# ModMicroController.net
KiCad netlist of a schematic drawn in Altium Designer
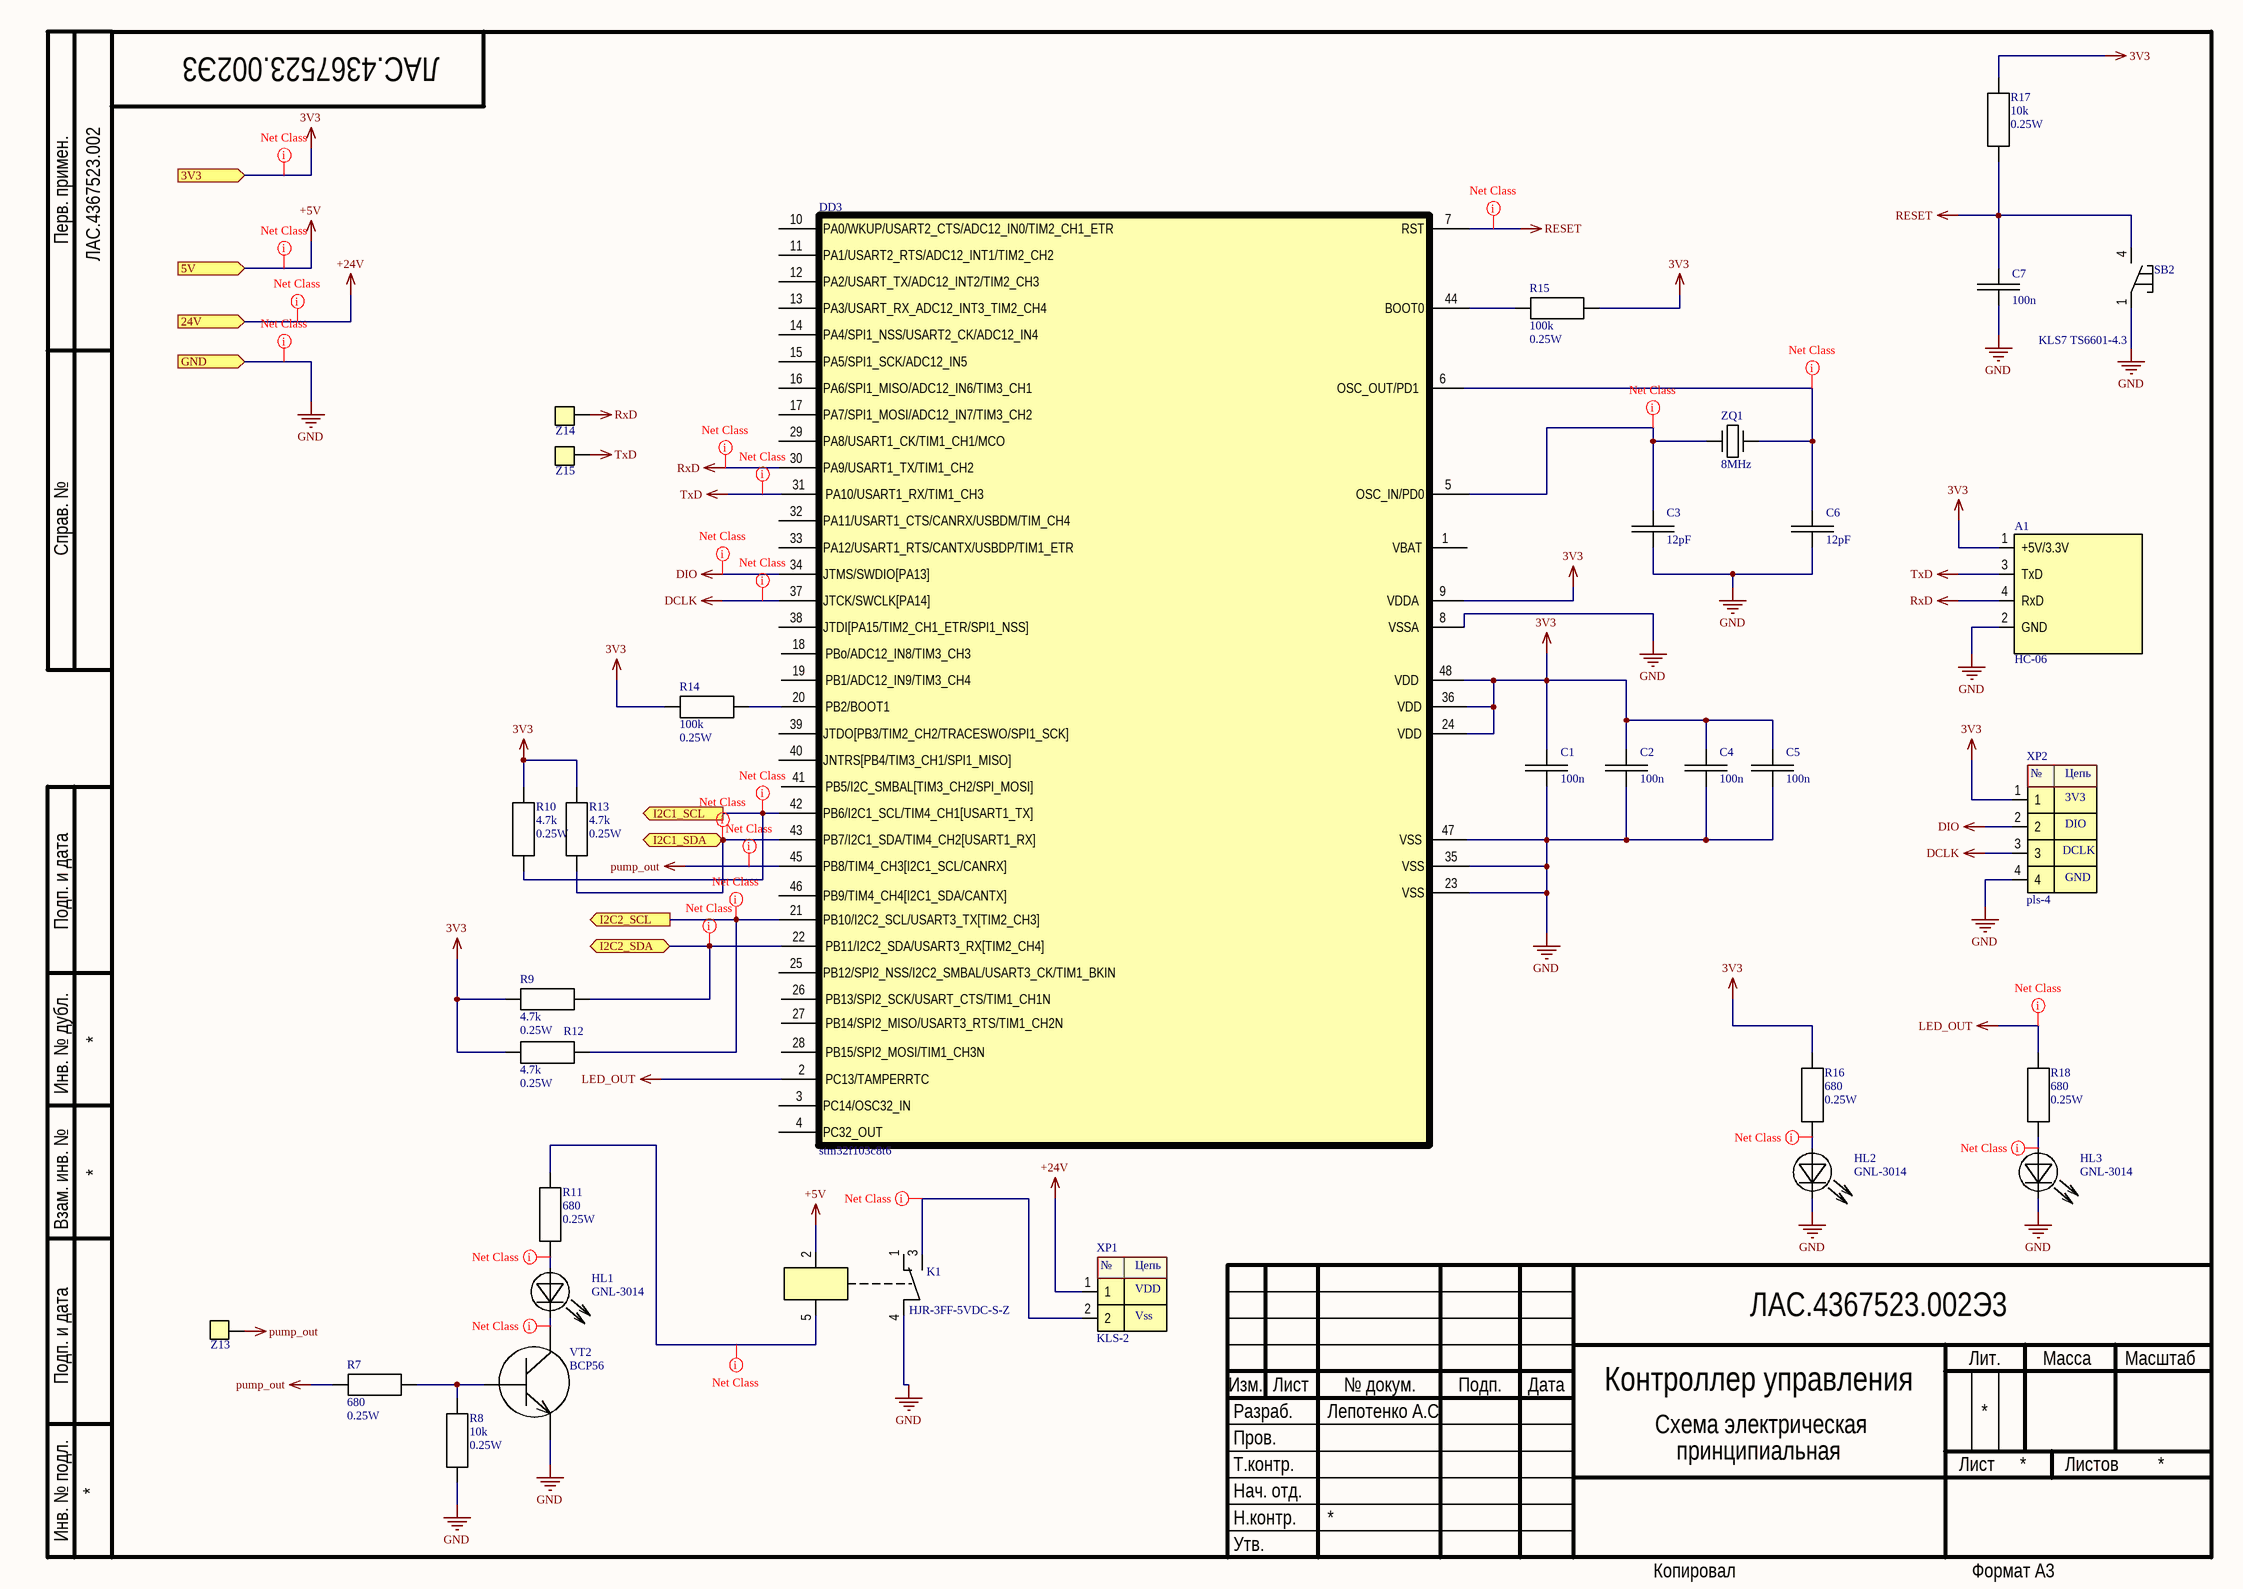
[diagram p0: ModMicroController.SchDoc]

(export (version "E")
  (design (tool "Eeschema 10.0.6"))
  (components
    (comp (ref "A1")
      (value "HC-06")
      (footprint "HC-06")
      (fields (field (name "MANUFACTURER") "china"))
      (libsource (lib "SchlibUGO") (part "HC-06"))
    )
    (comp (ref "C1")
      (value "100n")
      (footprint "CAP1206")
      (fields
        (field (name "VOLTAGE") "50V")
        (field (name "PART NUMBER") "CL31B104KBCNNNC")
        (field (name "MANUFACTURER") "Samsung")
      )
      (libsource (lib "SchlibUGO") (part "Capasitor"))
    )
    (comp (ref "C2")
      (value "100n")
      (footprint "CAP1206")
      (fields
        (field (name "VOLTAGE") "50V")
        (field (name "PART NUMBER") "CL31B104KBCNNNC")
        (field (name "MANUFACTURER") "Samsung")
      )
      (libsource (lib "SchlibUGO") (part "Capasitor"))
    )
    (comp (ref "C3")
      (value "12pF")
      (footprint "CAP1206")
      (fields
        (field (name "VOLTAGE") "50V")
        (field (name "PART NUMBER") "1206120NPO")
        (field (name "MANUFACTURER") "Samsung")
      )
      (libsource (lib "SchlibUGO") (part "Capasitor"))
    )
    (comp (ref "C4")
      (value "100n")
      (footprint "CAP1206")
      (fields
        (field (name "VOLTAGE") "50V")
        (field (name "PART NUMBER") "CL31B104KBCNNNC")
        (field (name "MANUFACTURER") "Samsung")
      )
      (libsource (lib "SchlibUGO") (part "Capasitor"))
    )
    (comp (ref "C5")
      (value "100n")
      (footprint "CAP1206")
      (fields
        (field (name "VOLTAGE") "50V")
        (field (name "PART NUMBER") "CL31B104KBCNNNC")
        (field (name "MANUFACTURER") "Samsung")
      )
      (libsource (lib "SchlibUGO") (part "Capasitor"))
    )
    (comp (ref "C6")
      (value "12pF")
      (footprint "CAP1206")
      (fields
        (field (name "VOLTAGE") "50V")
        (field (name "PART NUMBER") "1206120NPO")
        (field (name "MANUFACTURER") "Samsung")
      )
      (libsource (lib "SchlibUGO") (part "Capasitor"))
    )
    (comp (ref "C7") (value "100n") (footprint "CAP1206") (libsource (lib "SchlibUGO") (part "Capasitor")))
    (comp (ref "DD3")
      (value "stm32f103c8t6")
      (footprint "LQFP48")
      (fields (field (name "MANUFACTURER") "STM"))
      (libsource (lib "SchlibUGO") (part "stm32f103c8t6"))
    )
    (comp (ref "HL1")
      (value "GNL-3014")
      (footprint "GNL-3014")
      (fields (field (name "PART NUMBER") "GNL-3014SRD") (field (name "MANUFACTURER") "G-NOR"))
      (libsource (lib "SchlibUGO") (part "LED"))
    )
    (comp (ref "HL2")
      (value "GNL-3014")
      (footprint "GNL-3014")
      (fields (field (name "PART NUMBER") "GNL-3014SRD") (field (name "MANUFACTURER") "G-NOR"))
      (libsource (lib "SchlibUGO") (part "LED"))
    )
    (comp (ref "HL3")
      (value "GNL-3014")
      (footprint "GNL-3014")
      (fields (field (name "PART NUMBER") "GNL-3014SRD") (field (name "MANUFACTURER") "G-NOR"))
      (libsource (lib "SchlibUGO") (part "LED"))
    )
    (comp (ref "K1")
      (value "HJR-3FF-5VDC-S-Z")
      (footprint "HJR-3FF")
      (fields (field (name "MANUFACTURER") "TIANBO"))
      (libsource (lib "SchlibUGO") (part "HJR-3FF-5VDC-S-Z"))
    )
    (comp (ref "R7")
      (value "680")
      (footprint "1206")
      (fields
        (field (name "MANUFACTURER") "YAGEO")
        (field (name "PART NUMBER") "RC1206JR-07680RL")
        (field (name "POWER") "0.25W")
      )
      (libsource (lib "SchlibUGO") (part "Resistor"))
    )
    (comp (ref "R8")
      (value "10k")
      (footprint "1206")
      (fields
        (field (name "MANUFACTURER") "YAGEO")
        (field (name "PART NUMBER") "RC1206FR-0710KL")
        (field (name "POWER") "0.25W")
      )
      (libsource (lib "SchlibUGO") (part "Resistor"))
    )
    (comp (ref "R9")
      (value "4.7k")
      (footprint "1206")
      (fields
        (field (name "MANUFACTURER") "YAGEO")
        (field (name "PART NUMBER") "RC1206JR-074K7L")
        (field (name "POWER") "0.25W")
        (field (name "Comment") "4k7")
      )
      (libsource (lib "SchlibUGO") (part "Resistor"))
    )
    (comp (ref "R10")
      (value "4.7k")
      (footprint "1206")
      (fields
        (field (name "MANUFACTURER") "YAGEO")
        (field (name "PART NUMBER") "RC1206JR-074K7L")
        (field (name "POWER") "0.25W")
        (field (name "Comment") "4k7")
      )
      (libsource (lib "SchlibUGO") (part "Resistor"))
    )
    (comp (ref "R11")
      (value "680")
      (footprint "1206")
      (fields
        (field (name "MANUFACTURER") "YAGEO")
        (field (name "PART NUMBER") "RC1206JR-07680RL")
        (field (name "POWER") "0.25W")
      )
      (libsource (lib "SchlibUGO") (part "Resistor"))
    )
    (comp (ref "R12")
      (value "4.7k")
      (footprint "1206")
      (fields
        (field (name "MANUFACTURER") "YAGEO")
        (field (name "PART NUMBER") "RC1206JR-074K7L")
        (field (name "POWER") "0.25W")
        (field (name "Comment") "4k7")
      )
      (libsource (lib "SchlibUGO") (part "Resistor"))
    )
    (comp (ref "R13")
      (value "4.7k")
      (footprint "1206")
      (fields
        (field (name "MANUFACTURER") "YAGEO")
        (field (name "PART NUMBER") "RC1206JR-074K7L")
        (field (name "POWER") "0.25W")
        (field (name "Comment") "4k7")
      )
      (libsource (lib "SchlibUGO") (part "Resistor"))
    )
    (comp (ref "R14")
      (value "100k")
      (footprint "1206")
      (fields
        (field (name "MANUFACTURER") "YAGEO")
        (field (name "PART NUMBER") "RC1206JR-07100KL")
        (field (name "POWER") "0.25W")
        (field (name "Comment") "Resistor")
      )
      (libsource (lib "SchlibUGO") (part "Resistor"))
    )
    (comp (ref "R15")
      (value "100k")
      (footprint "1206")
      (fields
        (field (name "MANUFACTURER") "YAGEO")
        (field (name "PART NUMBER") "RC1206JR-07100KL")
        (field (name "POWER") "0.25W")
        (field (name "Comment") "Resistor")
      )
      (libsource (lib "SchlibUGO") (part "Resistor"))
    )
    (comp (ref "R16")
      (value "680")
      (footprint "1206")
      (fields
        (field (name "MANUFACTURER") "YAGEO")
        (field (name "PART NUMBER") "RC1206JR-07680RL")
        (field (name "POWER") "0.25W")
      )
      (libsource (lib "SchlibUGO") (part "Resistor"))
    )
    (comp (ref "R17")
      (value "10k")
      (footprint "1206")
      (fields
        (field (name "MANUFACTURER") "YAGEO")
        (field (name "PART NUMBER") "RC1206FR-0710KL")
        (field (name "POWER") "0.25W")
      )
      (libsource (lib "SchlibUGO") (part "Resistor"))
    )
    (comp (ref "R18")
      (value "680")
      (footprint "1206")
      (fields
        (field (name "MANUFACTURER") "YAGEO")
        (field (name "PART NUMBER") "RC1206JR-07680RL")
        (field (name "POWER") "0.25W")
      )
      (libsource (lib "SchlibUGO") (part "Resistor"))
    )
    (comp (ref "SB2")
      (value "KLS7 TS6601-4.3")
      (footprint "KLS2")
      (fields (field (name "MANUFACTURER") "KLS"))
      (libsource (lib "SchlibUGO") (part "Button"))
    )
    (comp (ref "VT2")
      (value "BCP56")
      (footprint "SOT223")
      (fields (field (name "PART NUMBER") "BCP56-16") (field (name "MANUFACTURER") "NXP Semiconductors"))
      (libsource (lib "SchlibUGO") (part "BCP56-16"))
    )
    (comp (ref "XP1")
      (value "KLS-2")
      (footprint "KLS2-EDR-500-2P")
      (fields (field (name "PART NUMBER") "KLS2-EDR"))
      (libsource (lib "SchlibUGO") (part "Connector_Power"))
    )
    (comp (ref "XP2")
      (value "pls-4")
      (footprint "Connector_STKLink")
      (fields (field (name "PART NUMBER") "pls-40") (field (name "MANUFACTURER") "RUICHI"))
      (libsource (lib "SchlibUGO") (part "Connector_STKLink"))
    )
    (comp (ref "Z13")
      (value "test Point")
      (footprint "test Point")
      (libsource (lib "") (part "test Point_1"))
    )
    (comp (ref "Z14")
      (value "test Point")
      (footprint "test Point")
      (libsource (lib "SchlibUGO") (part "test Point"))
    )
    (comp (ref "Z15")
      (value "test Point")
      (footprint "test Point")
      (libsource (lib "SchlibUGO") (part "test Point"))
    )
    (comp (ref "ZQ1")
      (value "8MHz")
      (footprint "HC-49US")
      (fields (field (name "PART NUMBER") "HC-49US") (field (name "MANUFACTURER") "GEYER"))
      (libsource (lib "SchlibUGO") (part "Rzanator"))
    )
  )
  (nets
    (net (code "1") (name "+5V") (class "Default")
      (node (ref "K1") (pin "2") (pinfunction "2_2") (pintype "passive"))
    )
    (net (code "2") (name "+24V") (class "Default")
      (node (ref "XP1") (pin "1") (pinfunction "1_1") (pintype "passive"))
    )
    (net (code "3") (name "/I2C1_SCL") (class "Default")
      (node (ref "DD3") (pin "42") (pinfunction "PB6/I2C1_SCL/TIM4_CH1[USART1_TX]_42") (pintype "passive"))
      (node (ref "R10") (pin "1") (pinfunction "1_1") (pintype "passive"))
    )
    (net (code "4") (name "/I2C1_SDA") (class "Default")
      (node (ref "DD3") (pin "43") (pinfunction "PB7/I2C1_SDA/TIM4_CH2[USART1_RX]_43") (pintype "passive"))
      (node (ref "R13") (pin "1") (pinfunction "1_1") (pintype "passive"))
    )
    (net (code "5") (name "/I2C2_SCL") (class "Default")
      (node (ref "DD3") (pin "21") (pinfunction "PB10/I2C2_SCL/USART3_TX[TIM2_CH3]_21") (pintype "passive"))
      (node (ref "R12") (pin "1") (pinfunction "1_1") (pintype "passive"))
    )
    (net (code "6") (name "/I2C2_SDA") (class "Default")
      (node (ref "DD3") (pin "22") (pinfunction "PB11/I2C2_SDA/USART3_RX[TIM2_CH4]_22") (pintype "passive"))
      (node (ref "R9") (pin "1") (pinfunction "1_1") (pintype "passive"))
    )
    (net (code "7") (name "3V3") (class "Default")
      (node (ref "A1") (pin "1") (pinfunction "+5V/3.3V_1") (pintype "passive"))
      (node (ref "C1") (pin "1") (pinfunction "1_1") (pintype "passive"))
      (node (ref "C2") (pin "1") (pinfunction "1_1") (pintype "passive"))
      (node (ref "C4") (pin "1") (pinfunction "1_1") (pintype "passive"))
      (node (ref "C5") (pin "1") (pinfunction "1_1") (pintype "passive"))
      (node (ref "DD3") (pin "24") (pinfunction "VDD_24") (pintype "passive"))
      (node (ref "DD3") (pin "36") (pinfunction "VDD_36") (pintype "passive"))
      (node (ref "DD3") (pin "48") (pinfunction "VDD_48") (pintype "passive"))
      (node (ref "DD3") (pin "9") (pinfunction "VDDA_9") (pintype "passive"))
      (node (ref "R10") (pin "2") (pinfunction "2_2") (pintype "passive"))
      (node (ref "R12") (pin "2") (pinfunction "2_2") (pintype "passive"))
      (node (ref "R13") (pin "2") (pinfunction "2_2") (pintype "passive"))
      (node (ref "R14") (pin "1") (pinfunction "1_1") (pintype "passive"))
      (node (ref "R15") (pin "2") (pinfunction "2_2") (pintype "passive"))
      (node (ref "R16") (pin "1") (pinfunction "1_1") (pintype "passive"))
      (node (ref "R17") (pin "2") (pinfunction "2_2") (pintype "passive"))
      (node (ref "R9") (pin "2") (pinfunction "2_2") (pintype "passive"))
      (node (ref "XP2") (pin "1") (pinfunction "1_1") (pintype "passive"))
    )
    (net (code "8") (name "DCLK") (class "Default")
      (node (ref "DD3") (pin "37") (pinfunction "JTCK/SWCLK[PA14]_37") (pintype "passive"))
      (node (ref "XP2") (pin "3") (pinfunction "3_3") (pintype "passive"))
    )
    (net (code "9") (name "DIO") (class "Default")
      (node (ref "DD3") (pin "34") (pinfunction "JTMS/SWDIO[PA13]_34") (pintype "passive"))
      (node (ref "XP2") (pin "2") (pinfunction "2_2") (pintype "passive"))
    )
    (net (code "10") (name "GND") (class "Default")
      (node (ref "A1") (pin "2") (pinfunction "GND_2") (pintype "passive"))
      (node (ref "C1") (pin "2") (pinfunction "2_2") (pintype "passive"))
      (node (ref "C2") (pin "2") (pinfunction "2_2") (pintype "passive"))
      (node (ref "C3") (pin "2") (pinfunction "2_2") (pintype "passive"))
      (node (ref "C4") (pin "2") (pinfunction "2_2") (pintype "passive"))
      (node (ref "C5") (pin "2") (pinfunction "2_2") (pintype "passive"))
      (node (ref "C6") (pin "2") (pinfunction "2_2") (pintype "passive"))
      (node (ref "C7") (pin "2") (pinfunction "2_2") (pintype "passive"))
      (node (ref "DD3") (pin "23") (pinfunction "VSS_23") (pintype "passive"))
      (node (ref "DD3") (pin "35") (pinfunction "VSS_35") (pintype "passive"))
      (node (ref "DD3") (pin "47") (pinfunction "VSS_47") (pintype "passive"))
      (node (ref "DD3") (pin "8") (pinfunction "VSSA_8") (pintype "passive"))
      (node (ref "HL2") (pin "2") (pinfunction "2_2") (pintype "passive"))
      (node (ref "HL3") (pin "2") (pinfunction "2_2") (pintype "passive"))
      (node (ref "K1") (pin "4") (pinfunction "4_4") (pintype "passive"))
      (node (ref "R8") (pin "1") (pinfunction "1_1") (pintype "passive"))
      (node (ref "SB2") (pin "1") (pinfunction "1_1") (pintype "passive"))
      (node (ref "VT2") (pin "3") (pinfunction "3_3") (pintype "passive"))
      (node (ref "XP2") (pin "4") (pinfunction "4_4") (pintype "passive"))
    )
    (net (code "11") (name "LED_OUT") (class "Default")
      (node (ref "DD3") (pin "2") (pinfunction "PC13/TAMPERRTC_2") (pintype "passive"))
      (node (ref "R18") (pin "1") (pinfunction "1_1") (pintype "passive"))
    )
    (net (code "12") (name "Net-(DD3-BOOT0)") (class "Default")
      (node (ref "DD3") (pin "44") (pinfunction "BOOT0_44") (pintype "passive"))
      (node (ref "R15") (pin "1") (pinfunction "1_1") (pintype "passive"))
    )
    (net (code "13") (name "Net-(DD3-OSC_IN{slash}PD0)") (class "Default")
      (node (ref "C3") (pin "1") (pinfunction "1_1") (pintype "passive"))
      (node (ref "DD3") (pin "5") (pinfunction "OSC_IN/PD0_5") (pintype "passive"))
      (node (ref "ZQ1") (pin "1") (pinfunction "1_1") (pintype "passive"))
    )
    (net (code "14") (name "Net-(DD3-OSC_OUT{slash}PD1)") (class "Default")
      (node (ref "C6") (pin "1") (pinfunction "1_1") (pintype "passive"))
      (node (ref "DD3") (pin "6") (pinfunction "OSC_OUT/PD1_6") (pintype "passive"))
      (node (ref "ZQ1") (pin "2") (pinfunction "2_2") (pintype "passive"))
    )
    (net (code "15") (name "Net-(DD3-PB2{slash}BOOT1)") (class "Default")
      (node (ref "DD3") (pin "20") (pinfunction "PB2/BOOT1_20") (pintype "passive"))
      (node (ref "R14") (pin "2") (pinfunction "2_2") (pintype "passive"))
    )
    (net (code "16") (name "Net-(HL1-Pad1)") (class "Default")
      (node (ref "HL1") (pin "1") (pinfunction "1_1") (pintype "passive"))
      (node (ref "R11") (pin "1") (pinfunction "1_1") (pintype "passive"))
    )
    (net (code "17") (name "Net-(HL1-Pad2)") (class "Default")
      (node (ref "HL1") (pin "2") (pinfunction "2_2") (pintype "passive"))
      (node (ref "VT2") (pin "2") (pinfunction "2_2") (pintype "passive"))
    )
    (net (code "18") (name "Net-(HL2-Pad1)") (class "Default")
      (node (ref "HL2") (pin "1") (pinfunction "1_1") (pintype "passive"))
      (node (ref "R16") (pin "2") (pinfunction "2_2") (pintype "passive"))
    )
    (net (code "19") (name "Net-(HL3-Pad1)") (class "Default")
      (node (ref "HL3") (pin "1") (pinfunction "1_1") (pintype "passive"))
      (node (ref "R18") (pin "2") (pinfunction "2_2") (pintype "passive"))
    )
    (net (code "20") (name "Net-(K1-Pad3)") (class "Default")
      (node (ref "K1") (pin "3") (pinfunction "3_3") (pintype "passive"))
      (node (ref "XP1") (pin "2") (pinfunction "2_2") (pintype "passive"))
    )
    (net (code "21") (name "Net-(K1-Pad5)") (class "Default")
      (node (ref "K1") (pin "5") (pinfunction "5_5") (pintype "passive"))
      (node (ref "R11") (pin "2") (pinfunction "2_2") (pintype "passive"))
    )
    (net (code "22") (name "Net-(R7-Pad1)") (class "Default")
      (node (ref "R7") (pin "1") (pinfunction "1_1") (pintype "passive"))
      (node (ref "R8") (pin "2") (pinfunction "2_2") (pintype "passive"))
      (node (ref "VT2") (pin "1") (pinfunction "1_1") (pintype "passive"))
    )
    (net (code "23") (name "RESET") (class "Default")
      (node (ref "C7") (pin "1") (pinfunction "1_1") (pintype "passive"))
      (node (ref "DD3") (pin "7") (pinfunction "RST_7") (pintype "passive"))
      (node (ref "R17") (pin "1") (pinfunction "1_1") (pintype "passive"))
      (node (ref "SB2") (pin "4") (pinfunction "4_4") (pintype "passive"))
    )
    (net (code "24") (name "RxD") (class "Default")
      (node (ref "A1") (pin "4") (pinfunction "RxD_4") (pintype "passive"))
      (node (ref "DD3") (pin "30") (pinfunction "PA9/USART1_TX/TIM1_CH2_30") (pintype "passive"))
      (node (ref "Z14") (pin "1") (pinfunction "1_1") (pintype "passive"))
    )
    (net (code "25") (name "TxD") (class "Default")
      (node (ref "A1") (pin "3") (pinfunction "TxD_3") (pintype "passive"))
      (node (ref "DD3") (pin "31") (pinfunction "PA10/USART1_RX/TIM1_CH3_31") (pintype "passive"))
      (node (ref "Z15") (pin "1") (pinfunction "1_1") (pintype "passive"))
    )
    (net (code "26") (name "pump_out") (class "Default")
      (node (ref "DD3") (pin "45") (pinfunction "PB8/TIM4_CH3[I2C1_SCL/CANRX]_45") (pintype "passive"))
      (node (ref "R7") (pin "2") (pinfunction "2_2") (pintype "passive"))
      (node (ref "Z13") (pin "1") (pinfunction "1_1") (pintype "passive"))
    )
    (net (code "27") (name "unconnected-(DD3-JNTRS[PB4{slash}TIM3_CH1{slash}SPI1_MISO]-Pad40)") (class "Default")
      (node (ref "DD3") (pin "40") (pinfunction "JNTRS[PB4/TIM3_CH1/SPI1_MISO]_40") (pintype "passive"))
    )
    (net (code "28") (name "unconnected-(DD3-JTDI[PA15{slash}TIM2_CH1_ETR{slash}SPI1_NSS]-Pad38)") (class "Default")
      (node (ref "DD3") (pin "38") (pinfunction "JTDI[PA15/TIM2_CH1_ETR/SPI1_NSS]_38") (pintype "passive"))
    )
    (net (code "29") (name "unconnected-(DD3-JTDO[PB3{slash}TIM2_CH2{slash}TRACESWO{slash}SPI1_SCK]-Pad39)") (class "Default")
      (node (ref "DD3") (pin "39") (pinfunction "JTDO[PB3/TIM2_CH2/TRACESWO/SPI1_SCK]_39") (pintype "passive"))
    )
    (net (code "30") (name "unconnected-(DD3-PA0{slash}WKUP{slash}USART2_CTS{slash}ADC12_IN0{slash}TIM2_CH1_ETR-Pad10)") (class "Default")
      (node (ref "DD3") (pin "10") (pinfunction "PA0/WKUP/USART2_CTS/ADC12_IN0/TIM2_CH1_ETR_10") (pintype "passive"))
    )
    (net (code "31") (name "unconnected-(DD3-PA1{slash}USART2_RTS{slash}ADC12_INT1{slash}TIM2_CH2-Pad11)") (class "Default")
      (node (ref "DD3") (pin "11") (pinfunction "PA1/USART2_RTS/ADC12_INT1/TIM2_CH2_11") (pintype "passive"))
    )
    (net (code "32") (name "unconnected-(DD3-PA2{slash}USART_TX{slash}ADC12_INT2{slash}TIM2_CH3-Pad12)") (class "Default")
      (node (ref "DD3") (pin "12") (pinfunction "PA2/USART_TX/ADC12_INT2/TIM2_CH3_12") (pintype "passive"))
    )
    (net (code "33") (name "unconnected-(DD3-PA3{slash}USART_RX_ADC12_INT3_TIM2_CH4-Pad13)") (class "Default")
      (node (ref "DD3") (pin "13") (pinfunction "PA3/USART_RX_ADC12_INT3_TIM2_CH4_13") (pintype "passive"))
    )
    (net (code "34") (name "unconnected-(DD3-PA4{slash}SPI1_NSS{slash}USART2_CK{slash}ADC12_IN4-Pad14)") (class "Default")
      (node (ref "DD3") (pin "14") (pinfunction "PA4/SPI1_NSS/USART2_CK/ADC12_IN4_14") (pintype "passive"))
    )
    (net (code "35") (name "unconnected-(DD3-PA5{slash}SPI1_SCK{slash}ADC12_IN5-Pad15)") (class "Default")
      (node (ref "DD3") (pin "15") (pinfunction "PA5/SPI1_SCK/ADC12_IN5_15") (pintype "passive"))
    )
    (net (code "36") (name "unconnected-(DD3-PA6{slash}SPI1_MISO{slash}ADC12_IN6{slash}TIM3_CH1-Pad16)") (class "Default")
      (node (ref "DD3") (pin "16") (pinfunction "PA6/SPI1_MISO/ADC12_IN6/TIM3_CH1_16") (pintype "passive"))
    )
    (net (code "37") (name "unconnected-(DD3-PA7{slash}SPI1_MOSI{slash}ADC12_IN7{slash}TIM3_CH2-Pad17)") (class "Default")
      (node (ref "DD3") (pin "17") (pinfunction "PA7/SPI1_MOSI/ADC12_IN7/TIM3_CH2_17") (pintype "passive"))
    )
    (net (code "38") (name "unconnected-(DD3-PA8{slash}USART1_CK{slash}TIM1_CH1{slash}MCO-Pad29)") (class "Default")
      (node (ref "DD3") (pin "29") (pinfunction "PA8/USART1_CK/TIM1_CH1/MCO_29") (pintype "passive"))
    )
    (net (code "39") (name "unconnected-(DD3-PA11{slash}USART1_CTS{slash}CANRX{slash}USBDM{slash}TIM_CH4-Pad32)") (class "Default")
      (node (ref "DD3") (pin "32") (pinfunction "PA11/USART1_CTS/CANRX/USBDM/TIM_CH4_32") (pintype "passive"))
    )
    (net (code "40") (name "unconnected-(DD3-PA12{slash}USART1_RTS{slash}CANTX{slash}USBDP{slash}TIM1_ETR-Pad33)") (class "Default")
      (node (ref "DD3") (pin "33") (pinfunction "PA12/USART1_RTS/CANTX/USBDP/TIM1_ETR_33") (pintype "passive"))
    )
    (net (code "41") (name "unconnected-(DD3-PB1{slash}ADC12_IN9{slash}TIM3_CH4-Pad19)") (class "Default")
      (node (ref "DD3") (pin "19") (pinfunction "PB1/ADC12_IN9/TIM3_CH4_19") (pintype "passive"))
    )
    (net (code "42") (name "unconnected-(DD3-PB5{slash}I2C_SMBAL[TIM3_CH2{slash}SPI_MOSI]-Pad41)") (class "Default")
      (node (ref "DD3") (pin "41") (pinfunction "PB5/I2C_SMBAL[TIM3_CH2/SPI_MOSI]_41") (pintype "passive"))
    )
    (net (code "43") (name "unconnected-(DD3-PB9{slash}TIM4_CH4[I2C1_SDA{slash}CANTX]-Pad46)") (class "Default")
      (node (ref "DD3") (pin "46") (pinfunction "PB9/TIM4_CH4[I2C1_SDA/CANTX]_46") (pintype "passive"))
    )
    (net (code "44") (name "unconnected-(DD3-PB12{slash}SPI2_NSS{slash}I2C2_SMBAL{slash}USART3_CK{slash}TIM1_BKIN-Pad25)") (class "Default")
      (node (ref "DD3") (pin "25") (pinfunction "PB12/SPI2_NSS/I2C2_SMBAL/USART3_CK/TIM1_BKIN_25") (pintype "passive"))
    )
    (net (code "45") (name "unconnected-(DD3-PB13{slash}SPI2_SCK{slash}USART_CTS{slash}TIM1_CH1N-Pad26)") (class "Default")
      (node (ref "DD3") (pin "26") (pinfunction "PB13/SPI2_SCK/USART_CTS/TIM1_CH1N_26") (pintype "passive"))
    )
    (net (code "46") (name "unconnected-(DD3-PB14{slash}SPI2_MISO{slash}USART3_RTS{slash}TIM1_CH2N-Pad27)") (class "Default")
      (node (ref "DD3") (pin "27") (pinfunction "PB14/SPI2_MISO/USART3_RTS/TIM1_CH2N_27") (pintype "passive"))
    )
    (net (code "47") (name "unconnected-(DD3-PB15{slash}SPI2_MOSI{slash}TIM1_CH3N-Pad28)") (class "Default")
      (node (ref "DD3") (pin "28") (pinfunction "PB15/SPI2_MOSI/TIM1_CH3N_28") (pintype "passive"))
    )
    (net (code "48") (name "unconnected-(DD3-PBo{slash}ADC12_IN8{slash}TIM3_CH3-Pad18)") (class "Default")
      (node (ref "DD3") (pin "18") (pinfunction "PBo/ADC12_IN8/TIM3_CH3_18") (pintype "passive"))
    )
    (net (code "49") (name "unconnected-(DD3-PC14{slash}OSC32_IN-Pad3)") (class "Default")
      (node (ref "DD3") (pin "3") (pinfunction "PC14/OSC32_IN_3") (pintype "passive"))
    )
    (net (code "50") (name "unconnected-(DD3-PC32_OUT-Pad4)") (class "Default")
      (node (ref "DD3") (pin "4") (pinfunction "PC32_OUT_4") (pintype "passive"))
    )
    (net (code "51") (name "unconnected-(DD3-VBAT-Pad1)") (class "Default")
      (node (ref "DD3") (pin "1") (pinfunction "VBAT_1") (pintype "passive"))
    )
    (net (code "52") (name "unconnected-(K1-Pad1)") (class "Default")
      (node (ref "K1") (pin "1") (pinfunction "1_1") (pintype "passive"))
    )
  )
)
